# CHIP_tzatziffy_v7.net
KiCad netlist of a schematic drawn in EAGLE
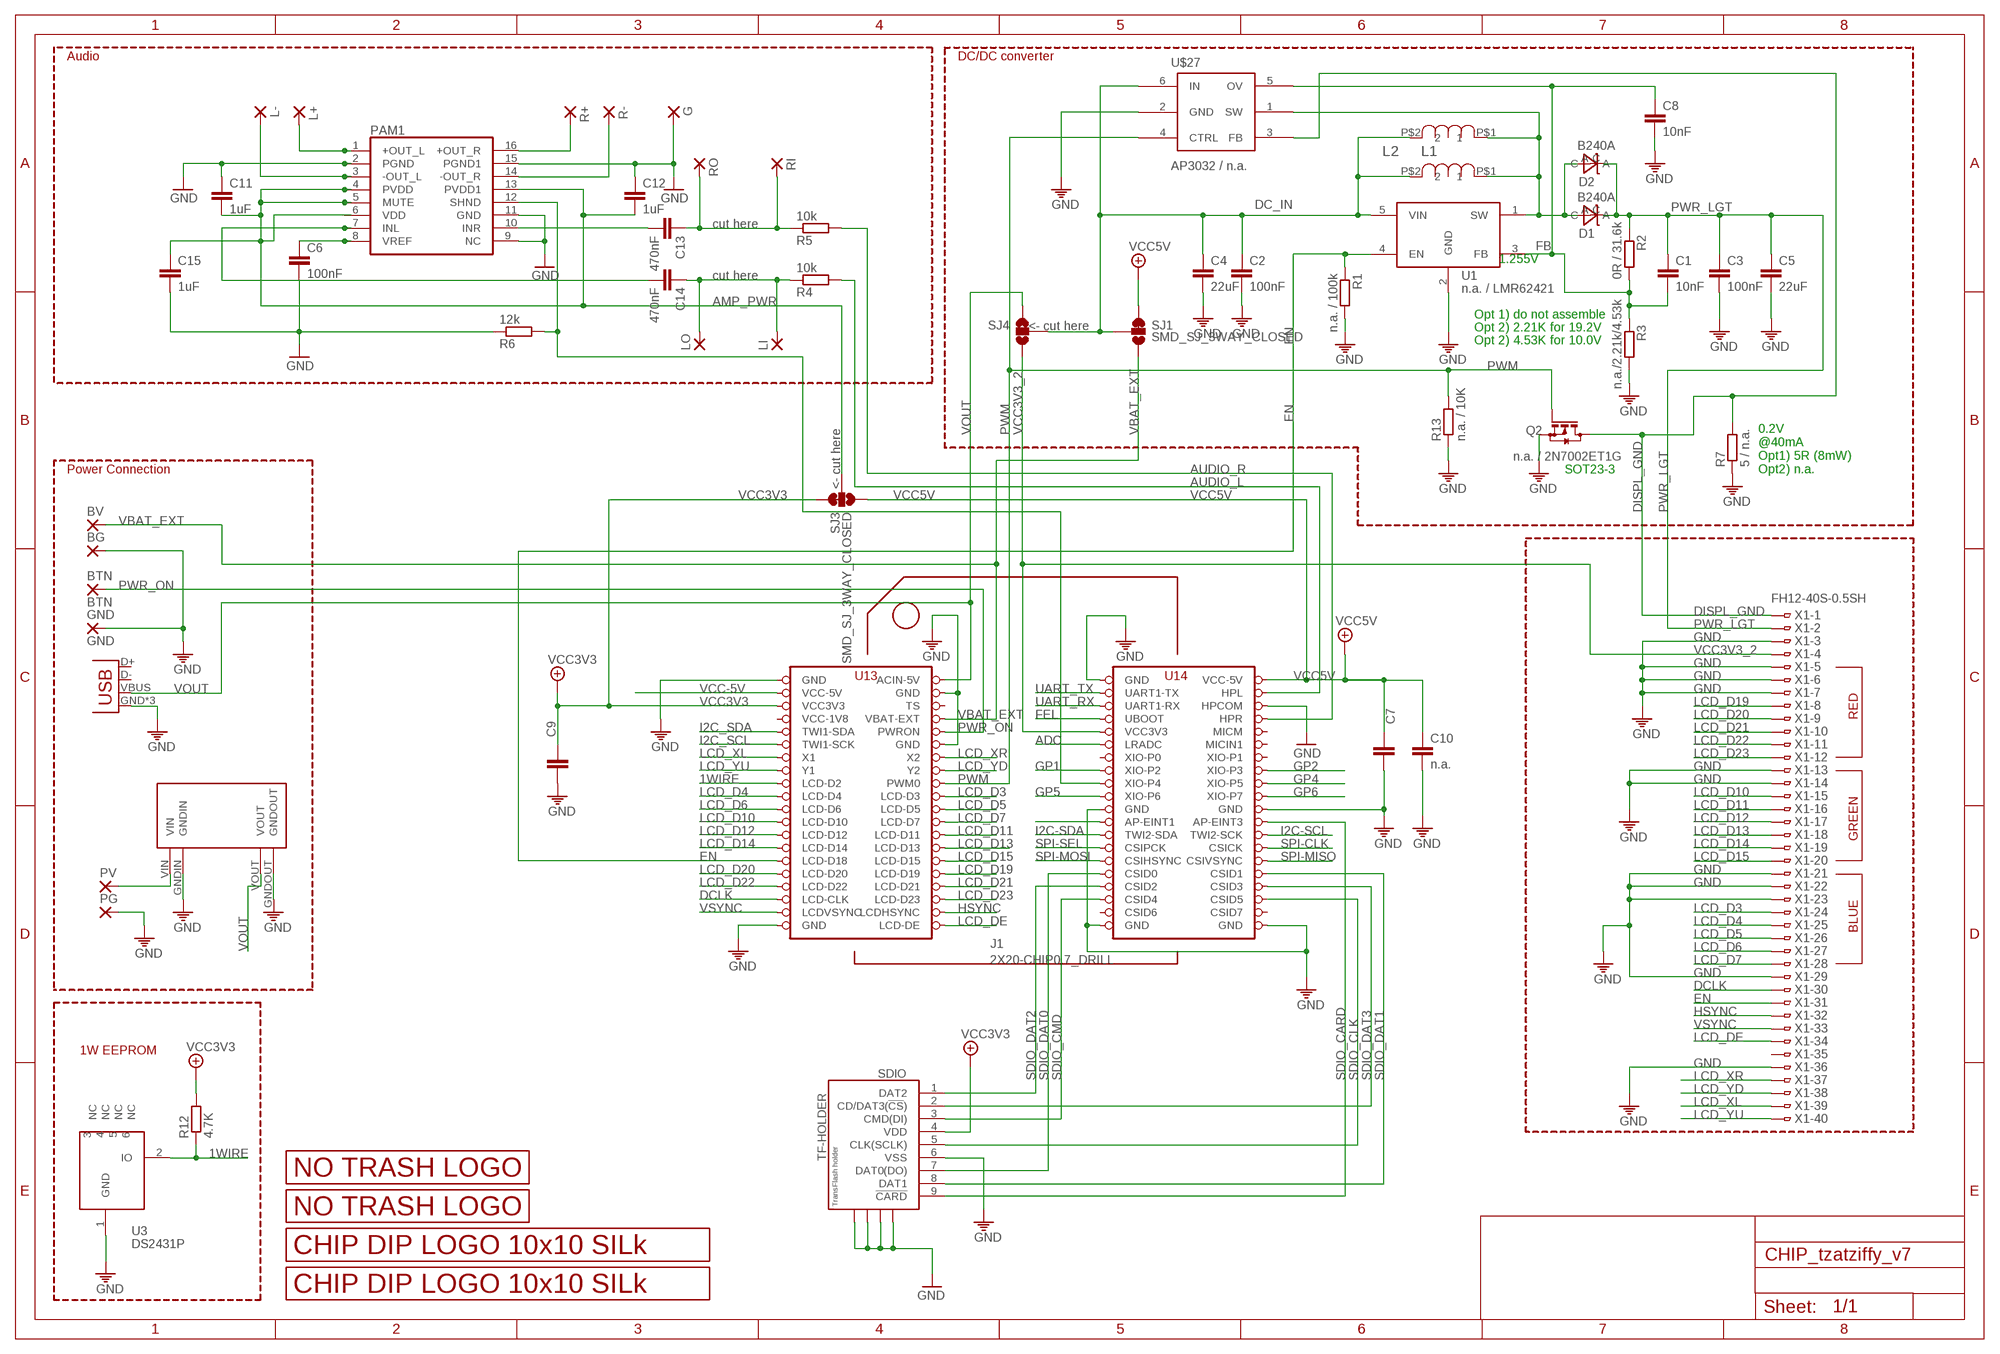
[diagram p0: schematic, sheet 1]

(export (version "E")
  (design (tool "Eeschema 10.0.6"))
  (components
    (comp (ref "BG")
      (value "1,6/0,8")
      (footprint "eagle-import:1,6_0,8")
      (libsource (lib "eagle-import") (part "1,6/0,8"))
    )
    (comp (ref "BTN")
      (value "BTN")
      (footprint "eagle-import:SMD1,27-2,54")
      (libsource (lib "eagle-import") (part "SMD2"))
    )
    (comp (ref "BV")
      (value "1,6/0,8")
      (footprint "eagle-import:1,6_0,8")
      (libsource (lib "eagle-import") (part "1,6/0,8"))
    )
    (comp (ref "C1")
      (value "10nF")
      (footprint "eagle-import:C0805")
      (libsource (lib "eagle-import") (part "C-EUC0805"))
    )
    (comp (ref "C2")
      (value "100nF")
      (footprint "eagle-import:C0805")
      (libsource (lib "eagle-import") (part "C-EUC0805"))
    )
    (comp (ref "C3")
      (value "100nF")
      (footprint "eagle-import:C0805")
      (libsource (lib "eagle-import") (part "C-EUC0805"))
    )
    (comp (ref "C4")
      (value "22uF")
      (footprint "eagle-import:C1206")
      (libsource (lib "eagle-import") (part "C-EUC1206"))
    )
    (comp (ref "C5")
      (value "22uF")
      (footprint "eagle-import:C1206")
      (libsource (lib "eagle-import") (part "C-EUC1206"))
    )
    (comp (ref "C6")
      (value "100nF")
      (footprint "eagle-import:C0805")
      (libsource (lib "eagle-import") (part "C-EUC0805"))
    )
    (comp (ref "C7")
      (value "n.a.")
      (footprint "eagle-import:C0805")
      (libsource (lib "eagle-import") (part "C-EUC0805"))
    )
    (comp (ref "C8")
      (value "10nF")
      (footprint "eagle-import:C0805")
      (libsource (lib "eagle-import") (part "C-EUC0805"))
    )
    (comp (ref "C9")
      (value "n.a.")
      (footprint "eagle-import:C0805")
      (libsource (lib "eagle-import") (part "C-EUC0805"))
    )
    (comp (ref "C10")
      (value "n.a.")
      (footprint "eagle-import:C0805")
      (libsource (lib "eagle-import") (part "C-EUC0805"))
    )
    (comp (ref "C11")
      (value "1uF")
      (footprint "eagle-import:C0805")
      (libsource (lib "eagle-import") (part "C-EUC0805"))
    )
    (comp (ref "C12")
      (value "1uF")
      (footprint "eagle-import:C0805")
      (libsource (lib "eagle-import") (part "C-EUC0805"))
    )
    (comp (ref "C13")
      (value "470nF")
      (footprint "eagle-import:C0805")
      (libsource (lib "eagle-import") (part "C-EUC0805"))
    )
    (comp (ref "C14")
      (value "470nF")
      (footprint "eagle-import:C0805")
      (libsource (lib "eagle-import") (part "C-EUC0805"))
    )
    (comp (ref "C15")
      (value "1uF")
      (footprint "eagle-import:C0805")
      (libsource (lib "eagle-import") (part "C-EUC0805"))
    )
    (comp (ref "D1")
      (value "B240A")
      (footprint "eagle-import:DO-214AC")
      (fields (field (name "MFG") "DIGIKEY") (field (name "VENDOR_PART_NUMBER") "B240A-13-F"))
      (libsource (lib "eagle-import") (part "DIODE_SCHTKY_B240"))
    )
    (comp (ref "D2")
      (value "B240A")
      (footprint "eagle-import:DO-214AC")
      (fields (field (name "MFG") "DIGIKEY") (field (name "VENDOR_PART_NUMBER") "B240A-13-F"))
      (libsource (lib "eagle-import") (part "DIODE_SCHTKY_B240"))
    )
    (comp (ref "G")
      (value "1,6/0,8")
      (footprint "eagle-import:1,6_0,8")
      (libsource (lib "eagle-import") (part "1,6/0,8"))
    )
    (comp (ref "GND")
      (value "GND")
      (footprint "eagle-import:SMD1,27-2,54")
      (libsource (lib "eagle-import") (part "SMD2"))
    )
    (comp (ref "J1")
      (value "2X20-CHIP0.7_DRILL")
      (footprint "eagle-import:2X20CHIP_NOOFFSET-TH_0.7")
      (libsource (lib "eagle-import") (part "2X20-CHIP0.7_DRILL"))
    )
    (comp (ref "L+")
      (value "1,6/0,8")
      (footprint "eagle-import:1,6_0,8")
      (libsource (lib "eagle-import") (part "1,6/0,8"))
    )
    (comp (ref "L-")
      (value "1,6/0,8")
      (footprint "eagle-import:1,6_0,8")
      (libsource (lib "eagle-import") (part "1,6/0,8"))
    )
    (comp (ref "L1")
      (value "SRN6045-100M")
      (footprint "eagle-import:SRN6045")
      (fields (field (name "MFG") "DIGIKEY"))
      (libsource (lib "eagle-import") (part "SRN6045-100M"))
    )
    (comp (ref "L2")
      (value "SRN6045-100M")
      (footprint "eagle-import:SRN6045")
      (fields (field (name "MFG") "DIGIKEY"))
      (libsource (lib "eagle-import") (part "SRN6045-100M"))
    )
    (comp (ref "LI")
      (value "1,6/0,8")
      (footprint "eagle-import:1,6_0,8")
      (libsource (lib "eagle-import") (part "1,6/0,8"))
    )
    (comp (ref "LO")
      (value "1,6/0,8")
      (footprint "eagle-import:1,6_0,8")
      (libsource (lib "eagle-import") (part "1,6/0,8"))
    )
    (comp (ref "PAM1")
      (value "PAM8403")
      (footprint "eagle-import:SOP-16")
      (libsource (lib "eagle-import") (part "PAM8403"))
    )
    (comp (ref "PG")
      (value "1,6/0,8")
      (footprint "eagle-import:1,6_0,8")
      (libsource (lib "eagle-import") (part "1,6/0,8"))
    )
    (comp (ref "PV")
      (value "1,6/0,8")
      (footprint "eagle-import:1,6_0,8")
      (libsource (lib "eagle-import") (part "1,6/0,8"))
    )
    (comp (ref "Q2")
      (value "n.a. / 2N7002ET1G")
      (footprint "eagle-import:SOT23")
      (libsource (lib "eagle-import") (part "BSS123"))
    )
    (comp (ref "R+")
      (value "1,6/0,8")
      (footprint "eagle-import:1,6_0,8")
      (libsource (lib "eagle-import") (part "1,6/0,8"))
    )
    (comp (ref "R-")
      (value "1,6/0,8")
      (footprint "eagle-import:1,6_0,8")
      (libsource (lib "eagle-import") (part "1,6/0,8"))
    )
    (comp (ref "R1")
      (value "n.a. / 100k")
      (footprint "eagle-import:M0805")
      (libsource (lib "eagle-import") (part "R-EU_M0805"))
    )
    (comp (ref "R2")
      (value "0R / 31.6k")
      (footprint "eagle-import:M0805")
      (libsource (lib "eagle-import") (part "R-EU_M0805"))
    )
    (comp (ref "R3")
      (value "n.a./2.21k/4.53k")
      (footprint "eagle-import:M0805")
      (libsource (lib "eagle-import") (part "R-EU_M0805"))
    )
    (comp (ref "R4")
      (value "10k")
      (footprint "eagle-import:R0805")
      (libsource (lib "eagle-import") (part "R-EU_R0805"))
    )
    (comp (ref "R5")
      (value "10k")
      (footprint "eagle-import:R0805")
      (libsource (lib "eagle-import") (part "R-EU_R0805"))
    )
    (comp (ref "R6")
      (value "12k")
      (footprint "eagle-import:R0805")
      (libsource (lib "eagle-import") (part "R-EU_R0805"))
    )
    (comp (ref "R7")
      (value "5 / n.a.")
      (footprint "eagle-import:M0805")
      (libsource (lib "eagle-import") (part "R-EU_M0805"))
    )
    (comp (ref "R12")
      (value "4.7K")
      (footprint "eagle-import:M0805")
      (libsource (lib "eagle-import") (part "R-EU_M0805"))
    )
    (comp (ref "R13")
      (value "n.a. / 10K")
      (footprint "eagle-import:M0805")
      (libsource (lib "eagle-import") (part "R-EU_M0805"))
    )
    (comp (ref "RI")
      (value "1,6/0,8")
      (footprint "eagle-import:1,6_0,8")
      (libsource (lib "eagle-import") (part "1,6/0,8"))
    )
    (comp (ref "RO")
      (value "1,6/0,8")
      (footprint "eagle-import:1,6_0,8")
      (libsource (lib "eagle-import") (part "1,6/0,8"))
    )
    (comp (ref "SDIO")
      (value "TF-HOLDER")
      (footprint "eagle-import:TF-PULL")
      (libsource (lib "eagle-import") (part "TF-HOLDER"))
    )
    (comp (ref "SJ1")
      (value "SMD_SJ_3WAY_CLOSED")
      (footprint "eagle-import:SMD_SJ_3WAY_CLOSED")
      (libsource (lib "eagle-import") (part "SMD_SJ_3WAY_CLOSED"))
    )
    (comp (ref "SJ3")
      (value "SMD_SJ_3WAY_CLOSED")
      (footprint "eagle-import:SMD_SJ_3WAY_CLOSED")
      (libsource (lib "eagle-import") (part "SMD_SJ_3WAY_CLOSED"))
    )
    (comp (ref "SJ4")
      (value "SMD_SJ_3WAY_OPENT")
      (footprint "eagle-import:SMD_SJ_3WAY_OPEN")
      (libsource (lib "eagle-import") (part "SMD_SJ_3WAY_OPENT"))
    )
    (comp (ref "U$2")
      (value "LOGO_10X10_SILK")
      (footprint "eagle-import:LOGO2_10X10_SILK")
      (libsource (lib "eagle-import") (part "LOGO_10X10_SILK"))
    )
    (comp (ref "U$3")
      (value "LOGO_NO_TRASHROHS")
      (footprint "eagle-import:LOGO_ROHS_SYM")
      (libsource (lib "eagle-import") (part "LOGO_NO_TRASHROHS"))
    )
    (comp (ref "U$4")
      (value "LOGO_NO_TRASHNO_TRASH")
      (footprint "eagle-import:LOGO_ROHS_NO_TRASH")
      (libsource (lib "eagle-import") (part "LOGO_NO_TRASHNO_TRASH"))
    )
    (comp (ref "U$5")
      (value "LOGO_10X10_SILK")
      (footprint "eagle-import:LOGO2_10X10_SILK")
      (libsource (lib "eagle-import") (part "LOGO_10X10_SILK"))
    )
    (comp (ref "U$10")
      (value "MP1584EN_FRAMELESS")
      (footprint "eagle-import:MP1584EN_FRAMELESS")
      (libsource (lib "eagle-import") (part "MP1584EN_FRAMELESS"))
    )
    (comp (ref "U$27")
      (value "AP3032 / n.a.")
      (footprint "eagle-import:SOT23-6")
      (libsource (lib "eagle-import") (part "AP3032"))
    )
    (comp (ref "U1")
      (value "n.a. / LMR62421")
      (footprint "eagle-import:SOT23-5")
      (fields (field (name "MFG") "DIGIKEY") (field (name "VENDOR_PART_NUMBER") "LMR62421XMFE/NOPB"))
      (libsource (lib "eagle-import") (part "LMR62421"))
    )
    (comp (ref "U3")
      (value "DS2431P")
      (footprint "eagle-import:TSOC6")
      (fields (field (name "MFG") "DIGIKEY") (field (name "VENDOR_PART_NUMBER") "DS2431P+T&R"))
      (libsource (lib "eagle-import") (part "DS2431P"))
    )
    (comp (ref "USB")
      (value "USBUSB-MICROB-SMT-DIP")
      (footprint "eagle-import:USB-MICROB-SMT-DIP")
      (libsource (lib "eagle-import") (part "USBUSB-MICROB-SMT-DIP"))
    )
    (comp (ref "X1")
      (value "FH12-40S-0.5SH")
      (footprint "eagle-import:FH12-40S-0.5SH")
      (fields (field (name "MFG") "DIGIKEY") (field (name "VENDOR_PART_NUMBER") "FH12-40S-0.5SH(55)"))
      (libsource (lib "eagle-import") (part "FH12-40S-0.5SH"))
    )
  )
  (nets
    (net (code "1") (name "/1WIRE") (class "Default")
      (node (ref "J1") (pin "LCD-D2") (pinfunction "LCD-D2_LCD-D2") (pintype "passive"))
      (node (ref "R12") (pin "1") (pinfunction "1_1") (pintype "passive"))
      (node (ref "U3") (pin "2") (pinfunction "IO_2") (pintype "bidirectional"))
    )
    (net (code "2") (name "/ADC") (class "Default")
      (node (ref "J1") (pin "LRADC") (pinfunction "LRADC_LRADC") (pintype "passive"))
    )
    (net (code "3") (name "/AMP_PWR") (class "Default")
      (node (ref "C11") (pin "2") (pinfunction "2_2") (pintype "passive"))
      (node (ref "C12") (pin "2") (pinfunction "2_2") (pintype "passive"))
      (node (ref "C15") (pin "1") (pinfunction "1_1") (pintype "passive"))
      (node (ref "PAM1") (pin "13") (pinfunction "PVDD1_13") (pintype "output"))
      (node (ref "PAM1") (pin "4") (pinfunction "PVDD_4") (pintype "input"))
      (node (ref "PAM1") (pin "5") (pinfunction "MUTE_5") (pintype "input"))
      (node (ref "PAM1") (pin "6") (pinfunction "VDD_6") (pintype "input"))
      (node (ref "SJ3") (pin "2") (pinfunction "2_2") (pintype "passive"))
    )
    (net (code "4") (name "/AUDIO_L") (class "Default")
      (node (ref "J1") (pin "HPL") (pinfunction "HPL_HPL") (pintype "passive"))
      (node (ref "R4") (pin "2") (pinfunction "2_2") (pintype "passive"))
    )
    (net (code "5") (name "/AUDIO_R") (class "Default")
      (node (ref "J1") (pin "HPR") (pinfunction "HPR_HPR") (pintype "passive"))
      (node (ref "R5") (pin "2") (pinfunction "2_2") (pintype "passive"))
    )
    (net (code "6") (name "/DCLK") (class "Default")
      (node (ref "J1") (pin "LCD-CLK") (pinfunction "LCD-CLK_LCD-CLK") (pintype "passive"))
      (node (ref "X1") (pin "30") (pinfunction "1_30") (pintype "passive"))
    )
    (net (code "7") (name "/DC_IN") (class "Default")
      (node (ref "C2") (pin "1") (pinfunction "1_1") (pintype "passive"))
      (node (ref "C4") (pin "1") (pinfunction "1_1") (pintype "passive"))
      (node (ref "L1") (pin "P$2") (pinfunction "2_P$2") (pintype "passive"))
      (node (ref "L2") (pin "P$2") (pinfunction "2_P$2") (pintype "passive"))
      (node (ref "SJ1") (pin "2") (pinfunction "2_2") (pintype "passive"))
      (node (ref "SJ4") (pin "2") (pinfunction "2_2") (pintype "passive"))
      (node (ref "U$27") (pin "6") (pinfunction "IN_6") (pintype "power_in"))
      (node (ref "U1") (pin "5") (pinfunction "VIN_5") (pintype "bidirectional"))
    )
    (net (code "8") (name "/DISPL_GND") (class "Default")
      (node (ref "Q2") (pin "3") (pinfunction "D_3") (pintype "passive"))
      (node (ref "R7") (pin "2") (pinfunction "2_2") (pintype "passive"))
      (node (ref "U$27") (pin "3") (pinfunction "FB_3") (pintype "passive"))
      (node (ref "X1") (pin "1") (pinfunction "1_1") (pintype "passive"))
    )
    (net (code "9") (name "/EN") (class "Default")
      (node (ref "J1") (pin "LCD-D18") (pinfunction "LCD-D18_LCD-D18") (pintype "passive"))
      (node (ref "R1") (pin "1") (pinfunction "1_1") (pintype "passive"))
      (node (ref "U1") (pin "4") (pinfunction "EN_4") (pintype "bidirectional"))
      (node (ref "X1") (pin "31") (pinfunction "1_31") (pintype "passive"))
    )
    (net (code "10") (name "/FB") (class "Default")
      (node (ref "C1") (pin "2") (pinfunction "2_2") (pintype "passive"))
      (node (ref "C8") (pin "1") (pinfunction "1_1") (pintype "passive"))
      (node (ref "R2") (pin "2") (pinfunction "2_2") (pintype "passive"))
      (node (ref "R3") (pin "1") (pinfunction "1_1") (pintype "passive"))
      (node (ref "U$27") (pin "5") (pinfunction "OV_5") (pintype "power_in"))
      (node (ref "U1") (pin "3") (pinfunction "FB_3") (pintype "bidirectional"))
    )
    (net (code "11") (name "/FEL") (class "Default")
      (node (ref "J1") (pin "FEL") (pinfunction "UBOOT_FEL") (pintype "passive"))
    )
    (net (code "12") (name "/GP1") (class "Default")
      (node (ref "J1") (pin "XIO-P2") (pinfunction "XIO-P2_XIO-P2") (pintype "passive"))
    )
    (net (code "13") (name "/GP2") (class "Default")
      (node (ref "J1") (pin "XIO-P3") (pinfunction "XIO-P3_XIO-P3") (pintype "passive"))
    )
    (net (code "14") (name "/GP4") (class "Default")
      (node (ref "J1") (pin "XIO-P5") (pinfunction "XIO-P5_XIO-P5") (pintype "passive"))
    )
    (net (code "15") (name "/GP5") (class "Default")
      (node (ref "J1") (pin "XIO-P6") (pinfunction "XIO-P6_XIO-P6") (pintype "passive"))
    )
    (net (code "16") (name "/GP6") (class "Default")
      (node (ref "J1") (pin "XIO-P7") (pinfunction "XIO-P7_XIO-P7") (pintype "passive"))
    )
    (net (code "17") (name "/HSYNC") (class "Default")
      (node (ref "J1") (pin "LCD-HSYNC") (pinfunction "LCDHSYNC_LCD-HSYNC") (pintype "passive"))
      (node (ref "X1") (pin "32") (pinfunction "1_32") (pintype "passive"))
    )
    (net (code "18") (name "/I2C-SCL") (class "Default")
      (node (ref "J1") (pin "TWI2-SCK") (pinfunction "TWI2-SCK_TWI2-SCK") (pintype "passive"))
    )
    (net (code "19") (name "/I2C-SDA") (class "Default")
      (node (ref "J1") (pin "TWI2-SDA") (pinfunction "TWI2-SDA_TWI2-SDA") (pintype "passive"))
    )
    (net (code "20") (name "/I2C_SCL") (class "Default")
      (node (ref "J1") (pin "TWI1-SCK") (pinfunction "TWI1-SCK_TWI1-SCK") (pintype "passive"))
    )
    (net (code "21") (name "/I2C_SDA") (class "Default")
      (node (ref "J1") (pin "TWI1-SDA") (pinfunction "TWI1-SDA_TWI1-SDA") (pintype "passive"))
    )
    (net (code "22") (name "/LCD_D3") (class "Default")
      (node (ref "J1") (pin "LCD-D3") (pinfunction "LCD-D3_LCD-D3") (pintype "passive"))
      (node (ref "X1") (pin "24") (pinfunction "1_24") (pintype "passive"))
    )
    (net (code "23") (name "/LCD_D4") (class "Default")
      (node (ref "J1") (pin "LCD-D4") (pinfunction "LCD-D4_LCD-D4") (pintype "passive"))
      (node (ref "X1") (pin "25") (pinfunction "1_25") (pintype "passive"))
    )
    (net (code "24") (name "/LCD_D5") (class "Default")
      (node (ref "J1") (pin "LCD-D5") (pinfunction "LCD-D5_LCD-D5") (pintype "passive"))
      (node (ref "X1") (pin "26") (pinfunction "1_26") (pintype "passive"))
    )
    (net (code "25") (name "/LCD_D6") (class "Default")
      (node (ref "J1") (pin "LCD-D6") (pinfunction "LCD-D6_LCD-D6") (pintype "passive"))
      (node (ref "X1") (pin "27") (pinfunction "1_27") (pintype "passive"))
    )
    (net (code "26") (name "/LCD_D7") (class "Default")
      (node (ref "J1") (pin "LCD-D7") (pinfunction "LCD-D7_LCD-D7") (pintype "passive"))
      (node (ref "X1") (pin "28") (pinfunction "1_28") (pintype "passive"))
    )
    (net (code "27") (name "/LCD_D10") (class "Default")
      (node (ref "J1") (pin "LCD-D10") (pinfunction "LCD-D10_LCD-D10") (pintype "passive"))
      (node (ref "X1") (pin "15") (pinfunction "1_15") (pintype "passive"))
    )
    (net (code "28") (name "/LCD_D11") (class "Default")
      (node (ref "J1") (pin "LCD-D11") (pinfunction "LCD-D11_LCD-D11") (pintype "passive"))
      (node (ref "X1") (pin "16") (pinfunction "1_16") (pintype "passive"))
    )
    (net (code "29") (name "/LCD_D12") (class "Default")
      (node (ref "J1") (pin "LCD-D12") (pinfunction "LCD-D12_LCD-D12") (pintype "passive"))
      (node (ref "X1") (pin "17") (pinfunction "1_17") (pintype "passive"))
    )
    (net (code "30") (name "/LCD_D13") (class "Default")
      (node (ref "J1") (pin "LCD-D13") (pinfunction "LCD-D13_LCD-D13") (pintype "passive"))
      (node (ref "X1") (pin "18") (pinfunction "1_18") (pintype "passive"))
    )
    (net (code "31") (name "/LCD_D14") (class "Default")
      (node (ref "J1") (pin "LCD-D14") (pinfunction "LCD-D14_LCD-D14") (pintype "passive"))
      (node (ref "X1") (pin "19") (pinfunction "1_19") (pintype "passive"))
    )
    (net (code "32") (name "/LCD_D15") (class "Default")
      (node (ref "J1") (pin "LCD-D15") (pinfunction "LCD-D15_LCD-D15") (pintype "passive"))
      (node (ref "X1") (pin "20") (pinfunction "1_20") (pintype "passive"))
    )
    (net (code "33") (name "/LCD_D19") (class "Default")
      (node (ref "J1") (pin "LCD-D19") (pinfunction "LCD-D19_LCD-D19") (pintype "passive"))
      (node (ref "X1") (pin "8") (pinfunction "1_8") (pintype "passive"))
    )
    (net (code "34") (name "/LCD_D20") (class "Default")
      (node (ref "J1") (pin "LCD-D20") (pinfunction "LCD-D20_LCD-D20") (pintype "passive"))
      (node (ref "X1") (pin "9") (pinfunction "1_9") (pintype "passive"))
    )
    (net (code "35") (name "/LCD_D21") (class "Default")
      (node (ref "J1") (pin "LCD-D21") (pinfunction "LCD-D21_LCD-D21") (pintype "passive"))
      (node (ref "X1") (pin "10") (pinfunction "1_10") (pintype "passive"))
    )
    (net (code "36") (name "/LCD_D22") (class "Default")
      (node (ref "J1") (pin "LCD-D22") (pinfunction "LCD-D22_LCD-D22") (pintype "passive"))
      (node (ref "X1") (pin "11") (pinfunction "1_11") (pintype "passive"))
    )
    (net (code "37") (name "/LCD_D23") (class "Default")
      (node (ref "J1") (pin "LCD-D23") (pinfunction "LCD-D23_LCD-D23") (pintype "passive"))
      (node (ref "X1") (pin "12") (pinfunction "1_12") (pintype "passive"))
    )
    (net (code "38") (name "/LCD_DE") (class "Default")
      (node (ref "J1") (pin "LCD-DE") (pinfunction "LCD-DE_LCD-DE") (pintype "passive"))
      (node (ref "X1") (pin "34") (pinfunction "1_34") (pintype "passive"))
    )
    (net (code "39") (name "/LCD_XL") (class "Default")
      (node (ref "J1") (pin "X1") (pinfunction "X1_X1") (pintype "passive"))
      (node (ref "X1") (pin "39") (pinfunction "1_39") (pintype "passive"))
    )
    (net (code "40") (name "/LCD_XR") (class "Default")
      (node (ref "J1") (pin "X2") (pinfunction "X2_X2") (pintype "passive"))
      (node (ref "X1") (pin "37") (pinfunction "1_37") (pintype "passive"))
    )
    (net (code "41") (name "/LCD_YD") (class "Default")
      (node (ref "J1") (pin "Y2") (pinfunction "Y2_Y2") (pintype "passive"))
      (node (ref "X1") (pin "38") (pinfunction "1_38") (pintype "passive"))
    )
    (net (code "42") (name "/LCD_YU") (class "Default")
      (node (ref "J1") (pin "Y1") (pinfunction "Y1_Y1") (pintype "passive"))
      (node (ref "X1") (pin "40") (pinfunction "1_40") (pintype "passive"))
    )
    (net (code "43") (name "/PWM") (class "Default")
      (node (ref "J1") (pin "PWM0") (pinfunction "PWM0_PWM0") (pintype "passive"))
      (node (ref "Q2") (pin "1") (pinfunction "G_1") (pintype "passive"))
      (node (ref "R13") (pin "2") (pinfunction "2_2") (pintype "passive"))
      (node (ref "U$27") (pin "4") (pinfunction "CTRL_4") (pintype "input"))
    )
    (net (code "44") (name "/PWR_LGT") (class "Default")
      (node (ref "C1") (pin "1") (pinfunction "1_1") (pintype "passive"))
      (node (ref "C3") (pin "1") (pinfunction "1_1") (pintype "passive"))
      (node (ref "C5") (pin "1") (pinfunction "1_1") (pintype "passive"))
      (node (ref "D1") (pin "C") (pinfunction "C_C") (pintype "bidirectional"))
      (node (ref "D2") (pin "C") (pinfunction "C_C") (pintype "bidirectional"))
      (node (ref "R2") (pin "1") (pinfunction "1_1") (pintype "passive"))
      (node (ref "X1") (pin "2") (pinfunction "1_2") (pintype "passive"))
    )
    (net (code "45") (name "/PWR_ON") (class "Default")
      (node (ref "BTN") (pin "1") (pinfunction "P_1") (pintype "passive"))
      (node (ref "J1") (pin "PWRON") (pinfunction "PWRON_PWRON") (pintype "passive"))
    )
    (net (code "46") (name "/SDIO_CARD") (class "Default")
      (node (ref "J1") (pin "AP-EINT3") (pinfunction "AP-EINT3_AP-EINT3") (pintype "passive"))
      (node (ref "SDIO") (pin "9") (pinfunction "~{CARD}_9") (pintype "passive"))
    )
    (net (code "47") (name "/SDIO_CLK") (class "Default")
      (node (ref "J1") (pin "CSID5") (pinfunction "CSID5_CSID5") (pintype "passive"))
      (node (ref "SDIO") (pin "5") (pinfunction "CLK(SCLK)_5") (pintype "input"))
    )
    (net (code "48") (name "/SDIO_CMD") (class "Default")
      (node (ref "J1") (pin "CSID4") (pinfunction "CSID4_CSID4") (pintype "passive"))
      (node (ref "SDIO") (pin "3") (pinfunction "CMD(DI)_3") (pintype "bidirectional"))
    )
    (net (code "49") (name "/SDIO_DAT0") (class "Default")
      (node (ref "J1") (pin "CSID0") (pinfunction "CSID0_CSID0") (pintype "passive"))
      (node (ref "SDIO") (pin "7") (pinfunction "DAT0(DO)_7") (pintype "bidirectional"))
    )
    (net (code "50") (name "/SDIO_DAT1") (class "Default")
      (node (ref "J1") (pin "CSID1") (pinfunction "CSID1_CSID1") (pintype "passive"))
      (node (ref "SDIO") (pin "8") (pinfunction "DAT1_8") (pintype "bidirectional"))
    )
    (net (code "51") (name "/SDIO_DAT2") (class "Default")
      (node (ref "J1") (pin "CSID2") (pinfunction "CSID2_CSID2") (pintype "passive"))
      (node (ref "SDIO") (pin "1") (pinfunction "DAT2_1") (pintype "bidirectional"))
    )
    (net (code "52") (name "/SDIO_DAT3") (class "Default")
      (node (ref "J1") (pin "CSID3") (pinfunction "CSID3_CSID3") (pintype "passive"))
      (node (ref "SDIO") (pin "2") (pinfunction "CD/DAT3(~{CS})_2") (pintype "bidirectional"))
    )
    (net (code "53") (name "/SPI-CLK") (class "Default")
      (node (ref "J1") (pin "CSICK") (pinfunction "CSICK_CSICK") (pintype "passive"))
    )
    (net (code "54") (name "/SPI-MISO") (class "Default")
      (node (ref "J1") (pin "CSIVSYNC") (pinfunction "CSIVSYNC_CSIVSYNC") (pintype "passive"))
    )
    (net (code "55") (name "/SPI-MOSI") (class "Default")
      (node (ref "J1") (pin "CSIHSYNC") (pinfunction "CSIHSYNC_CSIHSYNC") (pintype "passive"))
    )
    (net (code "56") (name "/SPI-SEL") (class "Default")
      (node (ref "J1") (pin "CSIPCK") (pinfunction "CSIPCK_CSIPCK") (pintype "passive"))
    )
    (net (code "57") (name "/UART_RX") (class "Default")
      (node (ref "J1") (pin "UART1-RX") (pinfunction "UART1-RX_UART1-RX") (pintype "passive"))
    )
    (net (code "58") (name "/UART_TX") (class "Default")
      (node (ref "J1") (pin "UART1-TX") (pinfunction "UART1-TX_UART1-TX") (pintype "passive"))
    )
    (net (code "59") (name "/VBAT_EXT") (class "Default")
      (node (ref "BV") (pin "1") (pinfunction "P_1") (pintype "passive"))
      (node (ref "J1") (pin "BAT") (pinfunction "VBAT-EXT_BAT") (pintype "passive"))
      (node (ref "SJ1") (pin "3") (pinfunction "3_3") (pintype "passive"))
    )
    (net (code "60") (name "/VCC-1V8") (class "Default")
      (node (ref "J1") (pin "VCC1V8") (pinfunction "VCC-1V8_VCC1V8") (pintype "power_in"))
    )
    (net (code "61") (name "/VCC-5V") (class "Default")
      (node (ref "J1") (pin "VCC5V@0") (pinfunction "VCC-5V_VCC5V@0") (pintype "power_in"))
    )
    (net (code "62") (name "/VCC3V3_2") (class "Default")
      (node (ref "J1") (pin "VCC3V3@1") (pinfunction "VCC3V3_VCC3V3@1") (pintype "power_in"))
      (node (ref "SJ4") (pin "3") (pinfunction "3_3") (pintype "passive"))
      (node (ref "X1") (pin "4") (pinfunction "1_4") (pintype "passive"))
    )
    (net (code "63") (name "/VOUT") (class "Default")
      (node (ref "J1") (pin "CHG-IN") (pinfunction "ACIN-5V_CHG-IN") (pintype "passive"))
      (node (ref "SJ4") (pin "1") (pinfunction "1_1") (pintype "passive"))
      (node (ref "U$10") (pin "VOUT") (pinfunction "VOUT_VOUT") (pintype "power_in"))
      (node (ref "USB") (pin "VBUS") (pinfunction "VBUS_VBUS") (pintype "bidirectional"))
    )
    (net (code "64") (name "/VSYNC") (class "Default")
      (node (ref "J1") (pin "LCD-VSYNC") (pinfunction "LCDVSYNC_LCD-VSYNC") (pintype "passive"))
      (node (ref "X1") (pin "33") (pinfunction "1_33") (pintype "passive"))
    )
    (net (code "65") (name "GND") (class "Default")
      (node (ref "BG") (pin "1") (pinfunction "P_1") (pintype "passive"))
      (node (ref "C10") (pin "2") (pinfunction "2_2") (pintype "passive"))
      (node (ref "C11") (pin "1") (pinfunction "1_1") (pintype "passive"))
      (node (ref "C12") (pin "1") (pinfunction "1_1") (pintype "passive"))
      (node (ref "C15") (pin "2") (pinfunction "2_2") (pintype "passive"))
      (node (ref "C2") (pin "2") (pinfunction "2_2") (pintype "passive"))
      (node (ref "C3") (pin "2") (pinfunction "2_2") (pintype "passive"))
      (node (ref "C4") (pin "2") (pinfunction "2_2") (pintype "passive"))
      (node (ref "C5") (pin "2") (pinfunction "2_2") (pintype "passive"))
      (node (ref "C6") (pin "2") (pinfunction "2_2") (pintype "passive"))
      (node (ref "C7") (pin "2") (pinfunction "2_2") (pintype "passive"))
      (node (ref "C8") (pin "2") (pinfunction "2_2") (pintype "passive"))
      (node (ref "C9") (pin "2") (pinfunction "2_2") (pintype "passive"))
      (node (ref "G") (pin "1") (pinfunction "P_1") (pintype "passive"))
      (node (ref "GND") (pin "1") (pinfunction "P_1") (pintype "passive"))
      (node (ref "J1") (pin "GND@1") (pinfunction "GND_GND@1") (pintype "power_in"))
      (node (ref "J1") (pin "GND@10") (pinfunction "GND_GND@10") (pintype "power_in"))
      (node (ref "J1") (pin "GND@2") (pinfunction "GND_GND@2") (pintype "power_in"))
      (node (ref "J1") (pin "GND@3") (pinfunction "GND_GND@3") (pintype "power_in"))
      (node (ref "J1") (pin "GND@4") (pinfunction "GND_GND@4") (pintype "power_in"))
      (node (ref "J1") (pin "GND@5") (pinfunction "GND_GND@5") (pintype "power_in"))
      (node (ref "J1") (pin "GND@6") (pinfunction "GND_GND@6") (pintype "power_in"))
      (node (ref "J1") (pin "GND@7") (pinfunction "GND_GND@7") (pintype "power_in"))
      (node (ref "J1") (pin "GND@8") (pinfunction "GND_GND@8") (pintype "power_in"))
      (node (ref "J1") (pin "HPCOM") (pinfunction "HPCOM_HPCOM") (pintype "passive"))
      (node (ref "PAM1") (pin "11") (pinfunction "GND_11") (pintype "output"))
      (node (ref "PAM1") (pin "15") (pinfunction "PGND1_15") (pintype "output"))
      (node (ref "PAM1") (pin "2") (pinfunction "PGND_2") (pintype "input"))
      (node (ref "PAM1") (pin "9") (pinfunction "NC_9") (pintype "output"))
      (node (ref "PG") (pin "1") (pinfunction "P_1") (pintype "passive"))
      (node (ref "Q2") (pin "2") (pinfunction "S_2") (pintype "passive"))
      (node (ref "R1") (pin "2") (pinfunction "2_2") (pintype "passive"))
      (node (ref "R13") (pin "1") (pinfunction "1_1") (pintype "passive"))
      (node (ref "R3") (pin "2") (pinfunction "2_2") (pintype "passive"))
      (node (ref "R6") (pin "1") (pinfunction "1_1") (pintype "passive"))
      (node (ref "R7") (pin "1") (pinfunction "1_1") (pintype "passive"))
      (node (ref "SDIO") (pin "6") (pinfunction "VSS_6") (pintype "power_in"))
      (node (ref "SDIO") (pin "S1") (pinfunction "S1_S1") (pintype "passive"))
      (node (ref "SDIO") (pin "S2") (pinfunction "S2_S2") (pintype "passive"))
      (node (ref "SDIO") (pin "S3") (pinfunction "S3_S3") (pintype "passive"))
      (node (ref "SDIO") (pin "S4") (pinfunction "S4_S4") (pintype "passive"))
      (node (ref "U$10") (pin "GNDIN") (pinfunction "GNDIN_GNDIN") (pintype "power_in"))
      (node (ref "U$10") (pin "GNDOUT") (pinfunction "GNDOUT_GNDOUT") (pintype "power_in"))
      (node (ref "U$27") (pin "2") (pinfunction "GND_2") (pintype "power_in"))
      (node (ref "U1") (pin "2") (pinfunction "GND_2") (pintype "bidirectional"))
      (node (ref "U3") (pin "1") (pinfunction "GND_1") (pintype "bidirectional"))
      (node (ref "USB") (pin "GND") (pinfunction "GND_GND") (pintype "bidirectional"))
      (node (ref "USB") (pin "MT1") (pinfunction "GND_MT1") (pintype "bidirectional"))
      (node (ref "USB") (pin "MT2") (pinfunction "GND_MT2") (pintype "bidirectional"))
      (node (ref "X1") (pin "13") (pinfunction "1_13") (pintype "passive"))
      (node (ref "X1") (pin "14") (pinfunction "1_14") (pintype "passive"))
      (node (ref "X1") (pin "21") (pinfunction "1_21") (pintype "passive"))
      (node (ref "X1") (pin "22") (pinfunction "1_22") (pintype "passive"))
      (node (ref "X1") (pin "23") (pinfunction "1_23") (pintype "passive"))
      (node (ref "X1") (pin "29") (pinfunction "1_29") (pintype "passive"))
      (node (ref "X1") (pin "3") (pinfunction "1_3") (pintype "passive"))
      (node (ref "X1") (pin "36") (pinfunction "1_36") (pintype "passive"))
      (node (ref "X1") (pin "5") (pinfunction "1_5") (pintype "passive"))
      (node (ref "X1") (pin "6") (pinfunction "1_6") (pintype "passive"))
      (node (ref "X1") (pin "7") (pinfunction "1_7") (pintype "passive"))
    )
    (net (code "66") (name "Net-(L+-P)") (class "Default")
      (node (ref "L+") (pin "1") (pinfunction "P_1") (pintype "passive"))
      (node (ref "PAM1") (pin "1") (pinfunction "+OUT_L_1") (pintype "input"))
    )
    (net (code "67") (name "Net-(L--P)") (class "Default")
      (node (ref "L-") (pin "1") (pinfunction "P_1") (pintype "passive"))
      (node (ref "PAM1") (pin "3") (pinfunction "-OUT_L_3") (pintype "input"))
    )
    (net (code "68") (name "Net-(L1-1)") (class "Default")
      (node (ref "D1") (pin "A") (pinfunction "A_A") (pintype "bidirectional"))
      (node (ref "D2") (pin "A") (pinfunction "A_A") (pintype "bidirectional"))
      (node (ref "L1") (pin "P$1") (pinfunction "1_P$1") (pintype "passive"))
      (node (ref "L2") (pin "P$1") (pinfunction "1_P$1") (pintype "passive"))
      (node (ref "U$27") (pin "1") (pinfunction "SW_1") (pintype "power_in"))
      (node (ref "U1") (pin "1") (pinfunction "SW_1") (pintype "bidirectional"))
    )
    (net (code "69") (name "Net-(LI-P)") (class "Default")
      (node (ref "C14") (pin "1") (pinfunction "1_1") (pintype "passive"))
      (node (ref "LI") (pin "1") (pinfunction "P_1") (pintype "passive"))
      (node (ref "LO") (pin "1") (pinfunction "P_1") (pintype "passive"))
      (node (ref "R4") (pin "1") (pinfunction "1_1") (pintype "passive"))
    )
    (net (code "70") (name "Net-(PAM1-+OUT_R)") (class "Default")
      (node (ref "PAM1") (pin "16") (pinfunction "+OUT_R_16") (pintype "output"))
      (node (ref "R+") (pin "1") (pinfunction "P_1") (pintype "passive"))
    )
    (net (code "71") (name "Net-(PAM1--OUT_R)") (class "Default")
      (node (ref "PAM1") (pin "14") (pinfunction "-OUT_R_14") (pintype "output"))
      (node (ref "R-") (pin "1") (pinfunction "P_1") (pintype "passive"))
    )
    (net (code "72") (name "Net-(PAM1-INL)") (class "Default")
      (node (ref "C14") (pin "2") (pinfunction "2_2") (pintype "passive"))
      (node (ref "PAM1") (pin "7") (pinfunction "INL_7") (pintype "input"))
    )
    (net (code "73") (name "Net-(PAM1-INR)") (class "Default")
      (node (ref "C13") (pin "2") (pinfunction "2_2") (pintype "passive"))
      (node (ref "PAM1") (pin "10") (pinfunction "INR_10") (pintype "output"))
    )
    (net (code "74") (name "Net-(PAM1-SHND)") (class "Default")
      (node (ref "J1") (pin "XIO-P4") (pinfunction "XIO-P4_XIO-P4") (pintype "passive"))
      (node (ref "PAM1") (pin "12") (pinfunction "SHND_12") (pintype "output"))
      (node (ref "R6") (pin "2") (pinfunction "2_2") (pintype "passive"))
    )
    (net (code "75") (name "Net-(PAM1-VREF)") (class "Default")
      (node (ref "C6") (pin "1") (pinfunction "1_1") (pintype "passive"))
      (node (ref "PAM1") (pin "8") (pinfunction "VREF_8") (pintype "input"))
    )
    (net (code "76") (name "Net-(PV-P)") (class "Default")
      (node (ref "PV") (pin "1") (pinfunction "P_1") (pintype "passive"))
      (node (ref "U$10") (pin "VIN") (pinfunction "VIN_VIN") (pintype "power_in"))
    )
    (net (code "77") (name "Net-(RI-P)") (class "Default")
      (node (ref "C13") (pin "1") (pinfunction "1_1") (pintype "passive"))
      (node (ref "R5") (pin "1") (pinfunction "1_1") (pintype "passive"))
      (node (ref "RI") (pin "1") (pinfunction "P_1") (pintype "passive"))
      (node (ref "RO") (pin "1") (pinfunction "P_1") (pintype "passive"))
    )
    (net (code "78") (name "VCC3V3") (class "Default")
      (node (ref "C9") (pin "1") (pinfunction "1_1") (pintype "passive"))
      (node (ref "J1") (pin "VCC3V3") (pinfunction "VCC3V3_VCC3V3") (pintype "power_in"))
      (node (ref "R12") (pin "2") (pinfunction "2_2") (pintype "passive"))
      (node (ref "SDIO") (pin "4") (pinfunction "VDD_4") (pintype "power_in"))
      (node (ref "SJ3") (pin "1") (pinfunction "1_1") (pintype "passive"))
    )
    (net (code "79") (name "VCC5V") (class "Default")
      (node (ref "C10") (pin "1") (pinfunction "1_1") (pintype "passive"))
      (node (ref "C7") (pin "1") (pinfunction "1_1") (pintype "passive"))
      (node (ref "J1") (pin "VCC5V@1") (pinfunction "VCC-5V_VCC5V@1") (pintype "power_in"))
      (node (ref "SJ1") (pin "1") (pinfunction "1_1") (pintype "passive"))
      (node (ref "SJ3") (pin "3") (pinfunction "3_3") (pintype "passive"))
    )
    (net (code "80") (name "unconnected-(J1-PadAP-EINT1)") (class "Default")
      (node (ref "J1") (pin "AP-EINT1") (pinfunction "AP-EINT1_AP-EINT1") (pintype "passive"))
    )
    (net (code "81") (name "unconnected-(J1-PadCSID6)") (class "Default")
      (node (ref "J1") (pin "CSID6") (pinfunction "CSID6_CSID6") (pintype "passive"))
    )
    (net (code "82") (name "unconnected-(J1-PadCSID7)") (class "Default")
      (node (ref "J1") (pin "CSID7") (pinfunction "CSID7_CSID7") (pintype "passive"))
    )
    (net (code "83") (name "unconnected-(J1-PadMICIN1)") (class "Default")
      (node (ref "J1") (pin "MICIN1") (pinfunction "MICIN1_MICIN1") (pintype "passive"))
    )
    (net (code "84") (name "unconnected-(J1-PadMICM)") (class "Default")
      (node (ref "J1") (pin "MICM") (pinfunction "MICM_MICM") (pintype "passive"))
    )
    (net (code "85") (name "unconnected-(J1-PadTS)") (class "Default")
      (node (ref "J1") (pin "TS") (pinfunction "TS_TS") (pintype "passive"))
    )
    (net (code "86") (name "unconnected-(J1-PadXIO-P0)") (class "Default")
      (node (ref "J1") (pin "XIO-P0") (pinfunction "XIO-P0_XIO-P0") (pintype "passive"))
    )
    (net (code "87") (name "unconnected-(J1-PadXIO-P1)") (class "Default")
      (node (ref "J1") (pin "XIO-P1") (pinfunction "XIO-P1_XIO-P1") (pintype "passive"))
    )
    (net (code "88") (name "unconnected-(U3-NC-Pad3)") (class "Default")
      (node (ref "U3") (pin "3") (pinfunction "NC_3") (pintype "bidirectional"))
    )
    (net (code "89") (name "unconnected-(U3-NC-Pad4)") (class "Default")
      (node (ref "U3") (pin "4") (pinfunction "NC_4") (pintype "bidirectional"))
    )
    (net (code "90") (name "unconnected-(U3-NC-Pad5)") (class "Default")
      (node (ref "U3") (pin "5") (pinfunction "NC_5") (pintype "bidirectional"))
    )
    (net (code "91") (name "unconnected-(U3-NC-Pad6)") (class "Default")
      (node (ref "U3") (pin "6") (pinfunction "NC_6") (pintype "bidirectional"))
    )
    (net (code "92") (name "unconnected-(USB-PadD+)") (class "Default")
      (node (ref "USB") (pin "D+") (pinfunction "D+_D+") (pintype "bidirectional"))
    )
    (net (code "93") (name "unconnected-(USB-PadD-)") (class "Default")
      (node (ref "USB") (pin "D-") (pinfunction "D-_D-") (pintype "bidirectional"))
    )
    (net (code "94") (name "unconnected-(X1AC-1-Pad35)") (class "Default")
      (node (ref "X1") (pin "35") (pinfunction "1_35") (pintype "passive"))
    )
  )
)
